# Petra.net
KiCad netlist of a schematic drawn in EAGLE
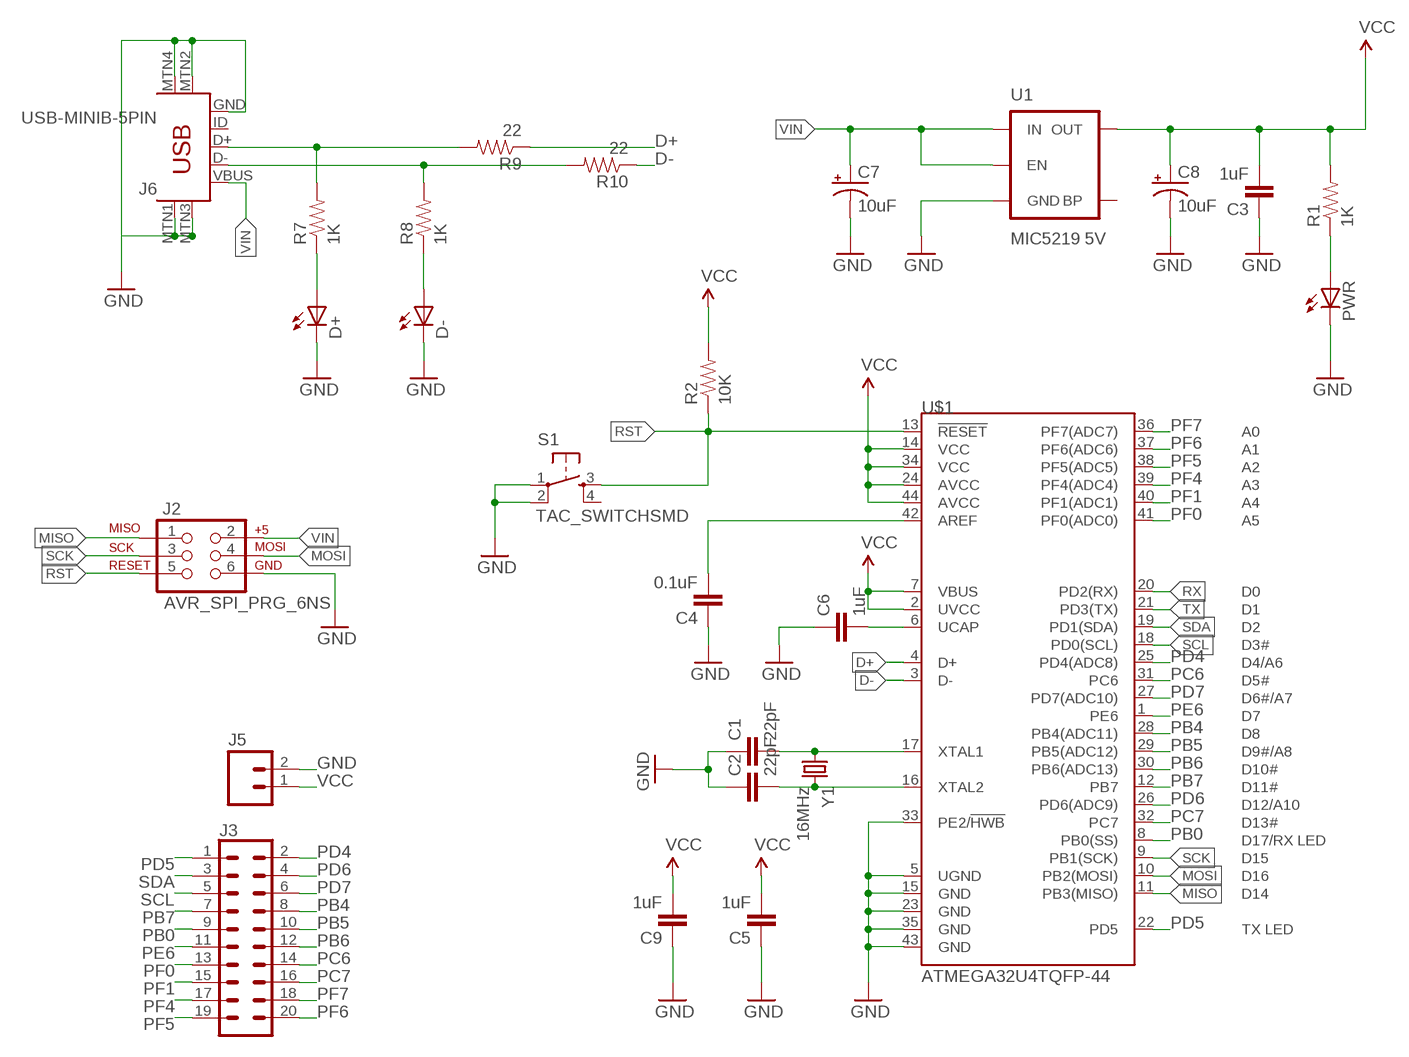
[diagram p0: schematic, sheet 1]

(export (version "E")
  (design (tool "Eeschema 10.0.6"))
  (components
    (comp (ref "C1")
      (value "22pF")
      (footprint "eagle-import:0402-CAP")
      (libsource (lib "eagle-import") (part "CAP0402-CAP"))
    )
    (comp (ref "C2")
      (value "22pF")
      (footprint "eagle-import:0402-CAP")
      (libsource (lib "eagle-import") (part "CAP0402-CAP"))
    )
    (comp (ref "C3")
      (value "1uF")
      (footprint "eagle-import:0402-CAP")
      (libsource (lib "eagle-import") (part "CAP0402-CAP"))
    )
    (comp (ref "C4")
      (value "0.1uF")
      (footprint "eagle-import:0402-CAP")
      (libsource (lib "eagle-import") (part "CAP0402-CAP"))
    )
    (comp (ref "C5")
      (value "1uF")
      (footprint "eagle-import:0402-CAP")
      (libsource (lib "eagle-import") (part "CAP0402-CAP"))
    )
    (comp (ref "C6")
      (value "1uF")
      (footprint "eagle-import:0402-CAP")
      (libsource (lib "eagle-import") (part "CAP0402-CAP"))
    )
    (comp (ref "C7")
      (value "10uF")
      (footprint "eagle-import:EIA3216")
      (libsource (lib "eagle-import") (part "CAP_POL1206"))
    )
    (comp (ref "C8")
      (value "10uF")
      (footprint "eagle-import:EIA3216")
      (libsource (lib "eagle-import") (part "CAP_POL1206"))
    )
    (comp (ref "C9")
      (value "1uF")
      (footprint "eagle-import:0402-CAP")
      (libsource (lib "eagle-import") (part "CAP0402-CAP"))
    )
    (comp (ref "D+")
      (value "LEDCHIP-LED0805")
      (footprint "eagle-import:CHIP-LED0805")
      (libsource (lib "eagle-import") (part "LEDCHIP-LED0805"))
    )
    (comp (ref "D-")
      (value "LEDCHIP-LED0805")
      (footprint "eagle-import:CHIP-LED0805")
      (libsource (lib "eagle-import") (part "LEDCHIP-LED0805"))
    )
    (comp (ref "J2")
      (value "AVR_SPI_PRG_6NS")
      (footprint "eagle-import:2X3-NS")
      (libsource (lib "eagle-import") (part "AVR_SPI_PRG_6NS"))
    )
    (comp (ref "J3")
      (value "CONN_10X2")
      (footprint "eagle-import:2X10")
      (libsource (lib "eagle-import") (part "CONN_10X2"))
    )
    (comp (ref "J5")
      (value "M02PTH")
      (footprint "eagle-import:1X02")
      (libsource (lib "eagle-import") (part "M02PTH"))
    )
    (comp (ref "J6")
      (value "USB-MINIB-5PIN")
      (footprint "eagle-import:USB-MINIB")
      (libsource (lib "eagle-import") (part "USB-MINIB-5PIN"))
    )
    (comp (ref "PWR")
      (value "LEDCHIP-LED0805")
      (footprint "eagle-import:CHIP-LED0805")
      (libsource (lib "eagle-import") (part "LEDCHIP-LED0805"))
    )
    (comp (ref "R1")
      (value "1K")
      (footprint "eagle-import:0603-RES")
      (libsource (lib "eagle-import") (part "10KOHM-1/10W-1%(0603)0603"))
    )
    (comp (ref "R2")
      (value "10K")
      (footprint "eagle-import:0603-RES")
      (libsource (lib "eagle-import") (part "10KOHM-1/10W-1%(0603)0603"))
    )
    (comp (ref "R7")
      (value "1K")
      (footprint "eagle-import:0603-RES")
      (libsource (lib "eagle-import") (part "10KOHM-1/10W-1%(0603)0603"))
    )
    (comp (ref "R8")
      (value "1K")
      (footprint "eagle-import:0603-RES")
      (libsource (lib "eagle-import") (part "10KOHM-1/10W-1%(0603)0603"))
    )
    (comp (ref "R9")
      (value "22")
      (footprint "eagle-import:0603-RES")
      (libsource (lib "eagle-import") (part "10KOHM-1/10W-1%(0603)0603"))
    )
    (comp (ref "R10")
      (value "22")
      (footprint "eagle-import:0603-RES")
      (libsource (lib "eagle-import") (part "10KOHM-1/10W-1%(0603)0603"))
    )
    (comp (ref "S1")
      (value "TAC_SWITCHSMD")
      (footprint "eagle-import:TAC-SWITCH-PTH")
      (libsource (lib "eagle-import") (part "TACTILE-SWITCH-PTH"))
    )
    (comp (ref "U$1")
      (value "ATMEGA32U4TQFP-44")
      (footprint "eagle-import:TQFP44")
      (libsource (lib "eagle-import") (part "ATMEGA32U4TQFP-44"))
    )
    (comp (ref "U1")
      (value "MIC5219 5V")
      (footprint "eagle-import:SOT23-5")
      (libsource (lib "eagle-import") (part "V_REG_MIC52195V"))
    )
    (comp (ref "Y1")
      (value "16MHz")
      (footprint "eagle-import:CRYSTAL-SMD-5X3")
      (libsource (lib "eagle-import") (part "CRYSTALCRYSTAL-SMD-5X3-16MHZ"))
    )
  )
  (nets
    (net (code "1") (name "/PB0") (class "Default")
      (node (ref "J3") (pin "9") (pinfunction "9_9") (pintype "passive"))
      (node (ref "U$1") (pin "8") (pinfunction "PB0(SS)_8") (pintype "bidirectional"))
    )
    (net (code "2") (name "/PB4") (class "Default")
      (node (ref "J3") (pin "8") (pinfunction "8_8") (pintype "passive"))
      (node (ref "U$1") (pin "28") (pinfunction "PB4(ADC11)_28") (pintype "bidirectional"))
    )
    (net (code "3") (name "/PB5") (class "Default")
      (node (ref "J3") (pin "10") (pinfunction "10_10") (pintype "passive"))
      (node (ref "U$1") (pin "29") (pinfunction "PB5(ADC12)_29") (pintype "bidirectional"))
    )
    (net (code "4") (name "/PB6") (class "Default")
      (node (ref "J3") (pin "12") (pinfunction "12_12") (pintype "passive"))
      (node (ref "U$1") (pin "30") (pinfunction "PB6(ADC13)_30") (pintype "bidirectional"))
    )
    (net (code "5") (name "/PB7") (class "Default")
      (node (ref "J3") (pin "7") (pinfunction "7_7") (pintype "passive"))
      (node (ref "U$1") (pin "12") (pinfunction "PB7_12") (pintype "bidirectional"))
    )
    (net (code "6") (name "/PC6") (class "Default")
      (node (ref "J3") (pin "14") (pinfunction "14_14") (pintype "passive"))
      (node (ref "U$1") (pin "31") (pinfunction "PC6_31") (pintype "bidirectional"))
    )
    (net (code "7") (name "/PC7") (class "Default")
      (node (ref "J3") (pin "16") (pinfunction "16_16") (pintype "passive"))
      (node (ref "U$1") (pin "32") (pinfunction "PC7_32") (pintype "bidirectional"))
    )
    (net (code "8") (name "/PD4") (class "Default")
      (node (ref "J3") (pin "2") (pinfunction "2_2") (pintype "passive"))
      (node (ref "U$1") (pin "25") (pinfunction "PD4(ADC8)_25") (pintype "bidirectional"))
    )
    (net (code "9") (name "/PD5") (class "Default")
      (node (ref "J3") (pin "1") (pinfunction "1_1") (pintype "passive"))
      (node (ref "U$1") (pin "22") (pinfunction "PD5_22") (pintype "bidirectional"))
    )
    (net (code "10") (name "/PD6") (class "Default")
      (node (ref "J3") (pin "4") (pinfunction "4_4") (pintype "passive"))
      (node (ref "U$1") (pin "26") (pinfunction "PD6(ADC9)_26") (pintype "bidirectional"))
    )
    (net (code "11") (name "/PD7") (class "Default")
      (node (ref "J3") (pin "6") (pinfunction "6_6") (pintype "passive"))
      (node (ref "U$1") (pin "27") (pinfunction "PD7(ADC10)_27") (pintype "bidirectional"))
    )
    (net (code "12") (name "/PE6") (class "Default")
      (node (ref "J3") (pin "11") (pinfunction "11_11") (pintype "passive"))
      (node (ref "U$1") (pin "1") (pinfunction "PE6_1") (pintype "bidirectional"))
    )
    (net (code "13") (name "/PF0") (class "Default")
      (node (ref "J3") (pin "13") (pinfunction "13_13") (pintype "passive"))
      (node (ref "U$1") (pin "41") (pinfunction "PF0(ADC0)_41") (pintype "bidirectional"))
    )
    (net (code "14") (name "/PF1") (class "Default")
      (node (ref "J3") (pin "15") (pinfunction "15_15") (pintype "passive"))
      (node (ref "U$1") (pin "40") (pinfunction "PF1(ADC1)_40") (pintype "bidirectional"))
    )
    (net (code "15") (name "/PF4") (class "Default")
      (node (ref "J3") (pin "17") (pinfunction "17_17") (pintype "passive"))
      (node (ref "U$1") (pin "39") (pinfunction "PF4(ADC4)_39") (pintype "bidirectional"))
    )
    (net (code "16") (name "/PF5") (class "Default")
      (node (ref "J3") (pin "19") (pinfunction "19_19") (pintype "passive"))
      (node (ref "U$1") (pin "38") (pinfunction "PF5(ADC5)_38") (pintype "bidirectional"))
    )
    (net (code "17") (name "/PF6") (class "Default")
      (node (ref "J3") (pin "20") (pinfunction "20_20") (pintype "passive"))
      (node (ref "U$1") (pin "37") (pinfunction "PF6(ADC6)_37") (pintype "bidirectional"))
    )
    (net (code "18") (name "/PF7") (class "Default")
      (node (ref "J3") (pin "18") (pinfunction "18_18") (pintype "passive"))
      (node (ref "U$1") (pin "36") (pinfunction "PF7(ADC7)_36") (pintype "bidirectional"))
    )
    (net (code "19") (name "D+") (class "Default")
      (node (ref "R9") (pin "1") (pinfunction "1_1") (pintype "passive"))
      (node (ref "U$1") (pin "4") (pinfunction "D+_4") (pintype "bidirectional"))
    )
    (net (code "20") (name "D-") (class "Default")
      (node (ref "R10") (pin "1") (pinfunction "1_1") (pintype "passive"))
      (node (ref "U$1") (pin "3") (pinfunction "D-_3") (pintype "bidirectional"))
    )
    (net (code "21") (name "GND") (class "Default")
      (node (ref "C1") (pin "1") (pinfunction "1_1") (pintype "passive"))
      (node (ref "C2") (pin "1") (pinfunction "1_1") (pintype "passive"))
      (node (ref "C3") (pin "1") (pinfunction "1_1") (pintype "passive"))
      (node (ref "C4") (pin "1") (pinfunction "1_1") (pintype "passive"))
      (node (ref "C5") (pin "1") (pinfunction "1_1") (pintype "passive"))
      (node (ref "C6") (pin "1") (pinfunction "1_1") (pintype "passive"))
      (node (ref "C7") (pin "C") (pinfunction "-_C") (pintype "passive"))
      (node (ref "C8") (pin "C") (pinfunction "-_C") (pintype "passive"))
      (node (ref "C9") (pin "1") (pinfunction "1_1") (pintype "passive"))
      (node (ref "D+") (pin "C") (pinfunction "C_C") (pintype "passive"))
      (node (ref "D-") (pin "C") (pinfunction "C_C") (pintype "passive"))
      (node (ref "J2") (pin "6") (pinfunction "6_6") (pintype "passive"))
      (node (ref "J5") (pin "2") (pinfunction "2_2") (pintype "passive"))
      (node (ref "J6") (pin "GND") (pinfunction "GND_GND") (pintype "bidirectional"))
      (node (ref "J6") (pin "MTN1") (pinfunction "MTN2_MTN1") (pintype "bidirectional"))
      (node (ref "J6") (pin "MTN2") (pinfunction "MTN3_MTN2") (pintype "bidirectional"))
      (node (ref "J6") (pin "MTN3") (pinfunction "MTN1_MTN3") (pintype "bidirectional"))
      (node (ref "J6") (pin "MTN4") (pinfunction "MTN4_MTN4") (pintype "bidirectional"))
      (node (ref "PWR") (pin "C") (pinfunction "C_C") (pintype "passive"))
      (node (ref "S1") (pin "1") (pinfunction "1_1") (pintype "passive"))
      (node (ref "S1") (pin "2") (pinfunction "2_2") (pintype "passive"))
      (node (ref "U$1") (pin "15") (pinfunction "GND_15") (pintype "bidirectional"))
      (node (ref "U$1") (pin "23") (pinfunction "GND_23") (pintype "bidirectional"))
      (node (ref "U$1") (pin "33") (pinfunction "PE2/~{HWB}_33") (pintype "bidirectional"))
      (node (ref "U$1") (pin "35") (pinfunction "GND_35") (pintype "bidirectional"))
      (node (ref "U$1") (pin "43") (pinfunction "GND_43") (pintype "bidirectional"))
      (node (ref "U$1") (pin "5") (pinfunction "UGND_5") (pintype "bidirectional"))
      (node (ref "U1") (pin "2") (pinfunction "GND_2") (pintype "input"))
    )
    (net (code "22") (name "MISO") (class "Default")
      (node (ref "J2") (pin "1") (pinfunction "1_1") (pintype "passive"))
      (node (ref "U$1") (pin "11") (pinfunction "PB3(MISO)_11") (pintype "bidirectional"))
    )
    (net (code "23") (name "MOSI") (class "Default")
      (node (ref "J2") (pin "4") (pinfunction "4_4") (pintype "passive"))
      (node (ref "U$1") (pin "10") (pinfunction "PB2(MOSI)_10") (pintype "bidirectional"))
    )
    (net (code "24") (name "Net-(D+-PadA)") (class "Default")
      (node (ref "D+") (pin "A") (pinfunction "A_A") (pintype "passive"))
      (node (ref "R7") (pin "1") (pinfunction "1_1") (pintype "passive"))
    )
    (net (code "25") (name "Net-(D--PadA)") (class "Default")
      (node (ref "D-") (pin "A") (pinfunction "A_A") (pintype "passive"))
      (node (ref "R8") (pin "1") (pinfunction "1_1") (pintype "passive"))
    )
    (net (code "26") (name "Net-(J6-PadD+)") (class "Default")
      (node (ref "J6") (pin "D+") (pinfunction "D+_D+") (pintype "bidirectional"))
      (node (ref "R7") (pin "2") (pinfunction "2_2") (pintype "passive"))
      (node (ref "R9") (pin "2") (pinfunction "2_2") (pintype "passive"))
    )
    (net (code "27") (name "Net-(J6-PadD-)") (class "Default")
      (node (ref "J6") (pin "D-") (pinfunction "D-_D-") (pintype "bidirectional"))
      (node (ref "R10") (pin "2") (pinfunction "2_2") (pintype "passive"))
      (node (ref "R8") (pin "2") (pinfunction "2_2") (pintype "passive"))
    )
    (net (code "28") (name "Net-(PWR-PadA)") (class "Default")
      (node (ref "PWR") (pin "A") (pinfunction "A_A") (pintype "passive"))
      (node (ref "R1") (pin "1") (pinfunction "1_1") (pintype "passive"))
    )
    (net (code "29") (name "Net-(U$1-AREF)") (class "Default")
      (node (ref "C4") (pin "2") (pinfunction "2_2") (pintype "passive"))
      (node (ref "U$1") (pin "42") (pinfunction "AREF_42") (pintype "bidirectional"))
    )
    (net (code "30") (name "Net-(U$1-UCAP)") (class "Default")
      (node (ref "C6") (pin "2") (pinfunction "2_2") (pintype "passive"))
      (node (ref "U$1") (pin "6") (pinfunction "UCAP_6") (pintype "bidirectional"))
    )
    (net (code "31") (name "Net-(U$1-XTAL1)") (class "Default")
      (node (ref "C1") (pin "2") (pinfunction "2_2") (pintype "passive"))
      (node (ref "U$1") (pin "17") (pinfunction "XTAL1_17") (pintype "bidirectional"))
      (node (ref "Y1") (pin "1") (pinfunction "1_1") (pintype "passive"))
    )
    (net (code "32") (name "Net-(U$1-XTAL2)") (class "Default")
      (node (ref "C2") (pin "2") (pinfunction "2_2") (pintype "passive"))
      (node (ref "U$1") (pin "16") (pinfunction "XTAL2_16") (pintype "bidirectional"))
      (node (ref "Y1") (pin "3") (pinfunction "2_3") (pintype "passive"))
    )
    (net (code "33") (name "RST") (class "Default")
      (node (ref "J2") (pin "5") (pinfunction "5_5") (pintype "passive"))
      (node (ref "R2") (pin "1") (pinfunction "1_1") (pintype "passive"))
      (node (ref "S1") (pin "3") (pinfunction "3_3") (pintype "passive"))
      (node (ref "U$1") (pin "13") (pinfunction "~{RESET}_13") (pintype "bidirectional"))
    )
    (net (code "34") (name "RX") (class "Default")
      (node (ref "U$1") (pin "20") (pinfunction "PD2(RX)_20") (pintype "bidirectional"))
    )
    (net (code "35") (name "SCK") (class "Default")
      (node (ref "J2") (pin "3") (pinfunction "3_3") (pintype "passive"))
      (node (ref "U$1") (pin "9") (pinfunction "PB1(SCK)_9") (pintype "bidirectional"))
    )
    (net (code "36") (name "SCL") (class "Default")
      (node (ref "J3") (pin "5") (pinfunction "5_5") (pintype "passive"))
      (node (ref "U$1") (pin "18") (pinfunction "PD0(SCL)_18") (pintype "bidirectional"))
    )
    (net (code "37") (name "SDA") (class "Default")
      (node (ref "J3") (pin "3") (pinfunction "3_3") (pintype "passive"))
      (node (ref "U$1") (pin "19") (pinfunction "PD1(SDA)_19") (pintype "bidirectional"))
    )
    (net (code "38") (name "TX") (class "Default")
      (node (ref "U$1") (pin "21") (pinfunction "PD3(TX)_21") (pintype "bidirectional"))
    )
    (net (code "39") (name "VCC") (class "Default")
      (node (ref "C3") (pin "2") (pinfunction "2_2") (pintype "passive"))
      (node (ref "C5") (pin "2") (pinfunction "2_2") (pintype "passive"))
      (node (ref "C8") (pin "A") (pinfunction "+_A") (pintype "passive"))
      (node (ref "C9") (pin "2") (pinfunction "2_2") (pintype "passive"))
      (node (ref "J5") (pin "1") (pinfunction "1_1") (pintype "passive"))
      (node (ref "R1") (pin "2") (pinfunction "2_2") (pintype "passive"))
      (node (ref "R2") (pin "2") (pinfunction "2_2") (pintype "passive"))
      (node (ref "U$1") (pin "14") (pinfunction "VCC_14") (pintype "bidirectional"))
      (node (ref "U$1") (pin "2") (pinfunction "UVCC_2") (pintype "bidirectional"))
      (node (ref "U$1") (pin "24") (pinfunction "AVCC_24") (pintype "bidirectional"))
      (node (ref "U$1") (pin "34") (pinfunction "VCC_34") (pintype "bidirectional"))
      (node (ref "U$1") (pin "44") (pinfunction "AVCC_44") (pintype "bidirectional"))
      (node (ref "U$1") (pin "7") (pinfunction "VBUS_7") (pintype "bidirectional"))
      (node (ref "U1") (pin "5") (pinfunction "OUT_5") (pintype "passive"))
    )
    (net (code "40") (name "VIN") (class "Default")
      (node (ref "C7") (pin "A") (pinfunction "+_A") (pintype "passive"))
      (node (ref "J2") (pin "2") (pinfunction "2_2") (pintype "passive"))
      (node (ref "J6") (pin "VBUS") (pinfunction "VBUS_VBUS") (pintype "bidirectional"))
      (node (ref "U1") (pin "1") (pinfunction "IN_1") (pintype "input"))
      (node (ref "U1") (pin "3") (pinfunction "EN_3") (pintype "input"))
    )
    (net (code "41") (name "unconnected-(J6-PadID)") (class "Default")
      (node (ref "J6") (pin "ID") (pinfunction "ID_ID") (pintype "bidirectional"))
    )
    (net (code "42") (name "unconnected-(S1-Pad4)") (class "Default")
      (node (ref "S1") (pin "4") (pinfunction "4_4") (pintype "passive"))
    )
    (net (code "43") (name "unconnected-(U1-BP-Pad4)") (class "Default")
      (node (ref "U1") (pin "4") (pinfunction "BP_4") (pintype "input"))
    )
  )
)
